# smoothieboard-glcd-adapter.net
KiCad netlist of a schematic drawn in EAGLE
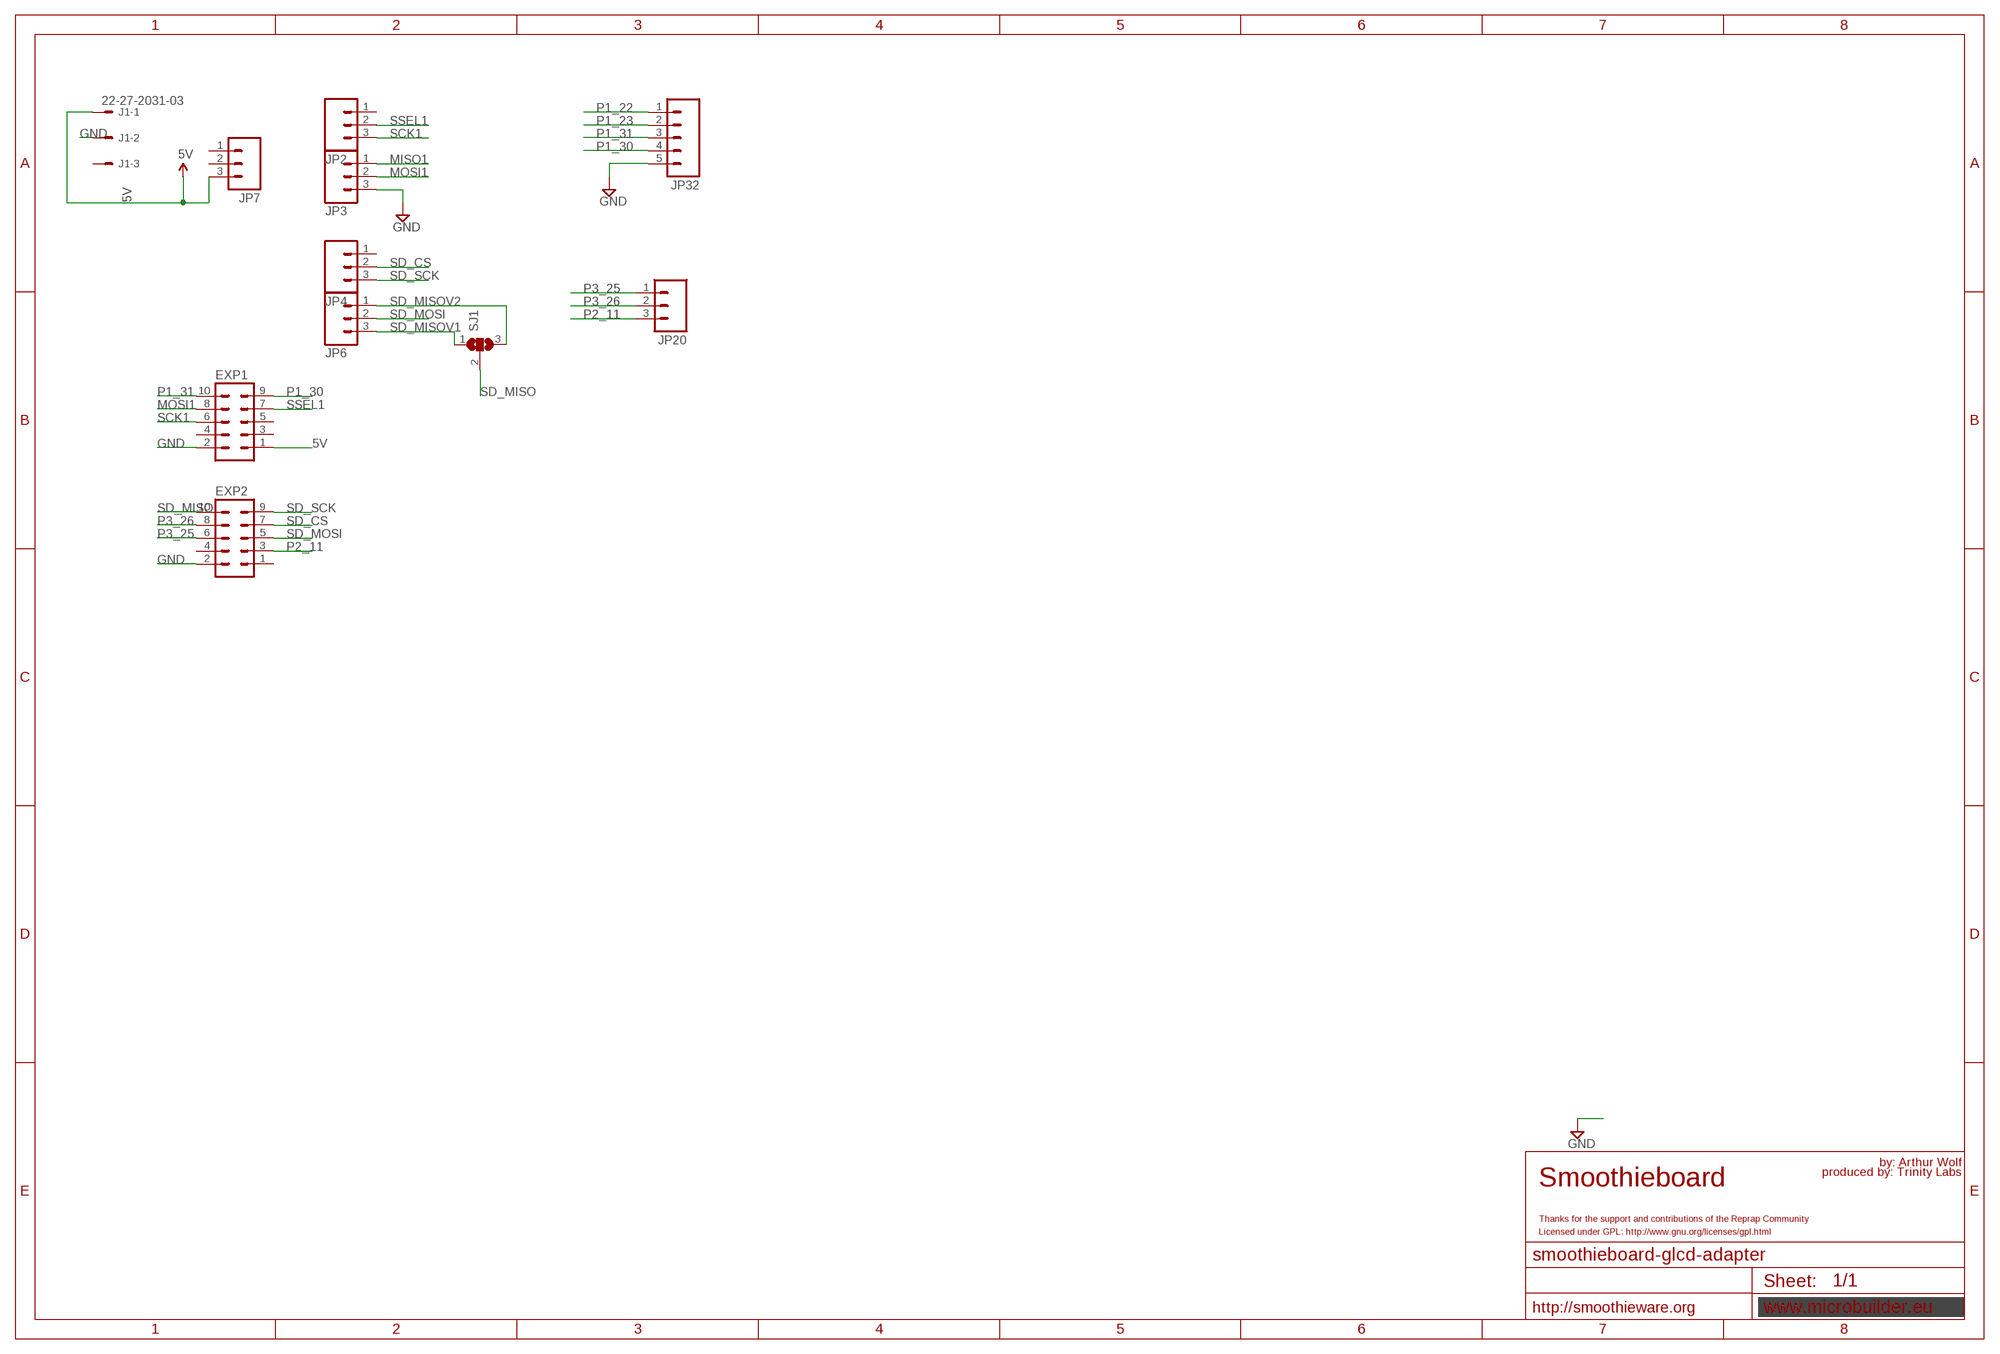
[diagram p0: schematic, sheet 1]

(export (version "E")
  (design (tool "Eeschema 10.0.6"))
  (components
    (comp (ref "EXP1")
      (value "ML10")
      (footprint "eagle-import:ML10")
      (libsource (lib "eagle-import") (part "ML10"))
    )
    (comp (ref "EXP2")
      (value "ML10")
      (footprint "eagle-import:ML10")
      (libsource (lib "eagle-import") (part "ML10"))
    )
    (comp (ref "J1")
      (value "22-27-2031-03")
      (footprint "eagle-import:6410-03")
      (libsource (lib "eagle-import") (part "22-?-0327-2031"))
    )
    (comp (ref "JP2")
      (value "M031X03_NO_SILK")
      (footprint "eagle-import:1X03_NO_SILK")
      (libsource (lib "eagle-import") (part "M031X03_NO_SILK"))
    )
    (comp (ref "JP3")
      (value "M031X03_NO_SILK")
      (footprint "eagle-import:1X03_NO_SILK")
      (libsource (lib "eagle-import") (part "M031X03_NO_SILK"))
    )
    (comp (ref "JP4")
      (value "M031X03_NO_SILK")
      (footprint "eagle-import:1X03_NO_SILK")
      (libsource (lib "eagle-import") (part "M031X03_NO_SILK"))
    )
    (comp (ref "JP6")
      (value "M031X03_NO_SILK")
      (footprint "eagle-import:1X03_NO_SILK")
      (libsource (lib "eagle-import") (part "M031X03_NO_SILK"))
    )
    (comp (ref "JP7")
      (value "M03PTH")
      (footprint "eagle-import:1X03")
      (libsource (lib "eagle-import") (part "M03PTH"))
    )
    (comp (ref "JP20")
      (value "M03PTH")
      (footprint "eagle-import:1X03")
      (libsource (lib "eagle-import") (part "M03PTH"))
    )
    (comp (ref "JP32")
      (value "M05PTH")
      (footprint "eagle-import:1X05")
      (libsource (lib "eagle-import") (part "M05PTH"))
    )
    (comp (ref "SJ1")
      (value "SJ2W")
      (footprint "eagle-import:SJ_2")
      (libsource (lib "eagle-import") (part "SJ2W"))
    )
  )
  (nets
    (net (code "1") (name "/MISO1") (class "Default")
      (node (ref "JP3") (pin "1") (pinfunction "1_1") (pintype "passive"))
    )
    (net (code "2") (name "/MOSI1") (class "Default")
      (node (ref "EXP1") (pin "8") (pinfunction "8_8") (pintype "passive"))
      (node (ref "JP3") (pin "2") (pinfunction "2_2") (pintype "passive"))
    )
    (net (code "3") (name "/P1_22") (class "Default")
      (node (ref "JP32") (pin "1") (pinfunction "1_1") (pintype "passive"))
    )
    (net (code "4") (name "/P1_23") (class "Default")
      (node (ref "JP32") (pin "2") (pinfunction "2_2") (pintype "passive"))
    )
    (net (code "5") (name "/P1_30") (class "Default")
      (node (ref "EXP1") (pin "9") (pinfunction "9_9") (pintype "passive"))
      (node (ref "JP32") (pin "4") (pinfunction "4_4") (pintype "passive"))
    )
    (net (code "6") (name "/P1_31") (class "Default")
      (node (ref "EXP1") (pin "10") (pinfunction "10_10") (pintype "passive"))
      (node (ref "JP32") (pin "3") (pinfunction "3_3") (pintype "passive"))
    )
    (net (code "7") (name "/P2_11") (class "Default")
      (node (ref "EXP2") (pin "3") (pinfunction "3_3") (pintype "passive"))
      (node (ref "JP20") (pin "3") (pinfunction "3_3") (pintype "passive"))
    )
    (net (code "8") (name "/P3_25") (class "Default")
      (node (ref "EXP2") (pin "6") (pinfunction "6_6") (pintype "passive"))
      (node (ref "JP20") (pin "1") (pinfunction "1_1") (pintype "passive"))
    )
    (net (code "9") (name "/P3_26") (class "Default")
      (node (ref "EXP2") (pin "8") (pinfunction "8_8") (pintype "passive"))
      (node (ref "JP20") (pin "2") (pinfunction "2_2") (pintype "passive"))
    )
    (net (code "10") (name "/SCK1") (class "Default")
      (node (ref "EXP1") (pin "6") (pinfunction "6_6") (pintype "passive"))
      (node (ref "JP2") (pin "3") (pinfunction "3_3") (pintype "passive"))
    )
    (net (code "11") (name "/SD_CS") (class "Default")
      (node (ref "EXP2") (pin "7") (pinfunction "7_7") (pintype "passive"))
      (node (ref "JP4") (pin "2") (pinfunction "2_2") (pintype "passive"))
    )
    (net (code "12") (name "/SD_MISO") (class "Default")
      (node (ref "EXP2") (pin "10") (pinfunction "10_10") (pintype "passive"))
      (node (ref "SJ1") (pin "2") (pinfunction "2_2") (pintype "passive"))
    )
    (net (code "13") (name "/SD_MISOV1") (class "Default")
      (node (ref "JP6") (pin "3") (pinfunction "3_3") (pintype "passive"))
      (node (ref "SJ1") (pin "1") (pinfunction "1_1") (pintype "passive"))
    )
    (net (code "14") (name "/SD_MISOV2") (class "Default")
      (node (ref "JP6") (pin "1") (pinfunction "1_1") (pintype "passive"))
      (node (ref "SJ1") (pin "3") (pinfunction "3_3") (pintype "passive"))
    )
    (net (code "15") (name "/SD_MOSI") (class "Default")
      (node (ref "EXP2") (pin "5") (pinfunction "5_5") (pintype "passive"))
      (node (ref "JP6") (pin "2") (pinfunction "2_2") (pintype "passive"))
    )
    (net (code "16") (name "/SD_SCK") (class "Default")
      (node (ref "EXP2") (pin "9") (pinfunction "9_9") (pintype "passive"))
      (node (ref "JP4") (pin "3") (pinfunction "3_3") (pintype "passive"))
    )
    (net (code "17") (name "/SSEL1") (class "Default")
      (node (ref "EXP1") (pin "7") (pinfunction "7_7") (pintype "passive"))
      (node (ref "JP2") (pin "2") (pinfunction "2_2") (pintype "passive"))
    )
    (net (code "18") (name "5V") (class "Default")
      (node (ref "EXP1") (pin "1") (pinfunction "1_1") (pintype "passive"))
      (node (ref "J1") (pin "1") (pinfunction "S_1") (pintype "passive"))
      (node (ref "JP7") (pin "3") (pinfunction "3_3") (pintype "passive"))
    )
    (net (code "19") (name "GND") (class "Default")
      (node (ref "EXP1") (pin "2") (pinfunction "2_2") (pintype "passive"))
      (node (ref "EXP2") (pin "2") (pinfunction "2_2") (pintype "passive"))
      (node (ref "J1") (pin "2") (pinfunction "S_2") (pintype "passive"))
      (node (ref "JP3") (pin "3") (pinfunction "3_3") (pintype "passive"))
      (node (ref "JP32") (pin "5") (pinfunction "5_5") (pintype "passive"))
    )
    (net (code "20") (name "unconnected-(EXP1-Pad3)") (class "Default")
      (node (ref "EXP1") (pin "3") (pinfunction "3_3") (pintype "passive"))
    )
    (net (code "21") (name "unconnected-(EXP1-Pad4)") (class "Default")
      (node (ref "EXP1") (pin "4") (pinfunction "4_4") (pintype "passive"))
    )
    (net (code "22") (name "unconnected-(EXP1-Pad5)") (class "Default")
      (node (ref "EXP1") (pin "5") (pinfunction "5_5") (pintype "passive"))
    )
    (net (code "23") (name "unconnected-(EXP2-Pad1)") (class "Default")
      (node (ref "EXP2") (pin "1") (pinfunction "1_1") (pintype "passive"))
    )
    (net (code "24") (name "unconnected-(EXP2-Pad4)") (class "Default")
      (node (ref "EXP2") (pin "4") (pinfunction "4_4") (pintype "passive"))
    )
    (net (code "25") (name "unconnected-(J1C-S-Pad3)") (class "Default")
      (node (ref "J1") (pin "3") (pinfunction "S_3") (pintype "passive"))
    )
    (net (code "26") (name "unconnected-(JP2-Pad1)") (class "Default")
      (node (ref "JP2") (pin "1") (pinfunction "1_1") (pintype "passive"))
    )
    (net (code "27") (name "unconnected-(JP4-Pad1)") (class "Default")
      (node (ref "JP4") (pin "1") (pinfunction "1_1") (pintype "passive"))
    )
    (net (code "28") (name "unconnected-(JP7-Pad1)") (class "Default")
      (node (ref "JP7") (pin "1") (pinfunction "1_1") (pintype "passive"))
    )
    (net (code "29") (name "unconnected-(JP7-Pad2)") (class "Default")
      (node (ref "JP7") (pin "2") (pinfunction "2_2") (pintype "passive"))
    )
  )
)
